# vr60.net
KiCad netlist of a schematic drawn in EAGLE
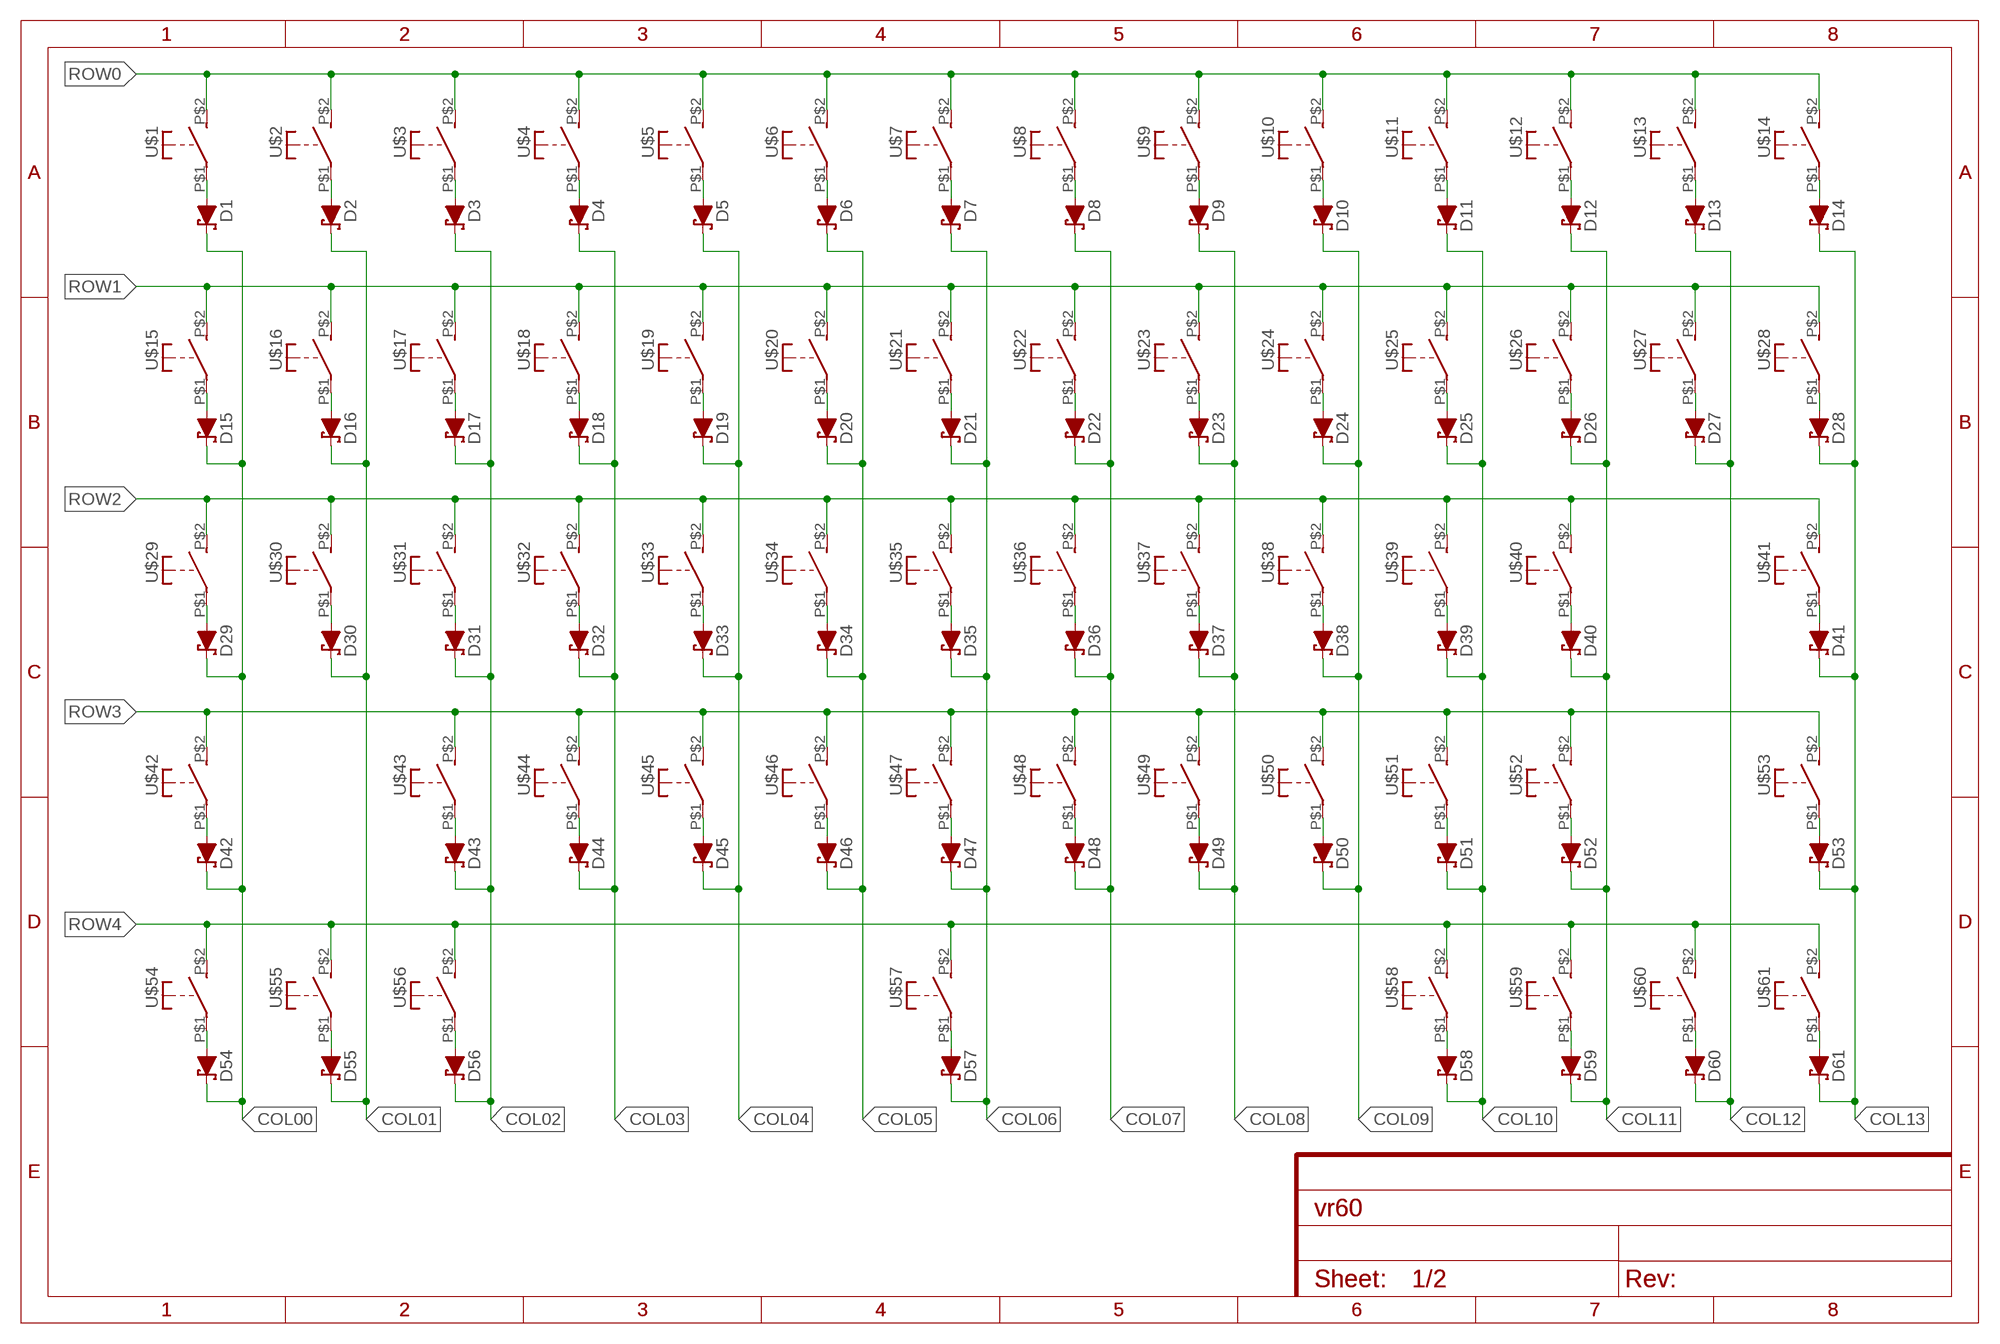
[diagram p0: schematic, sheet 1]
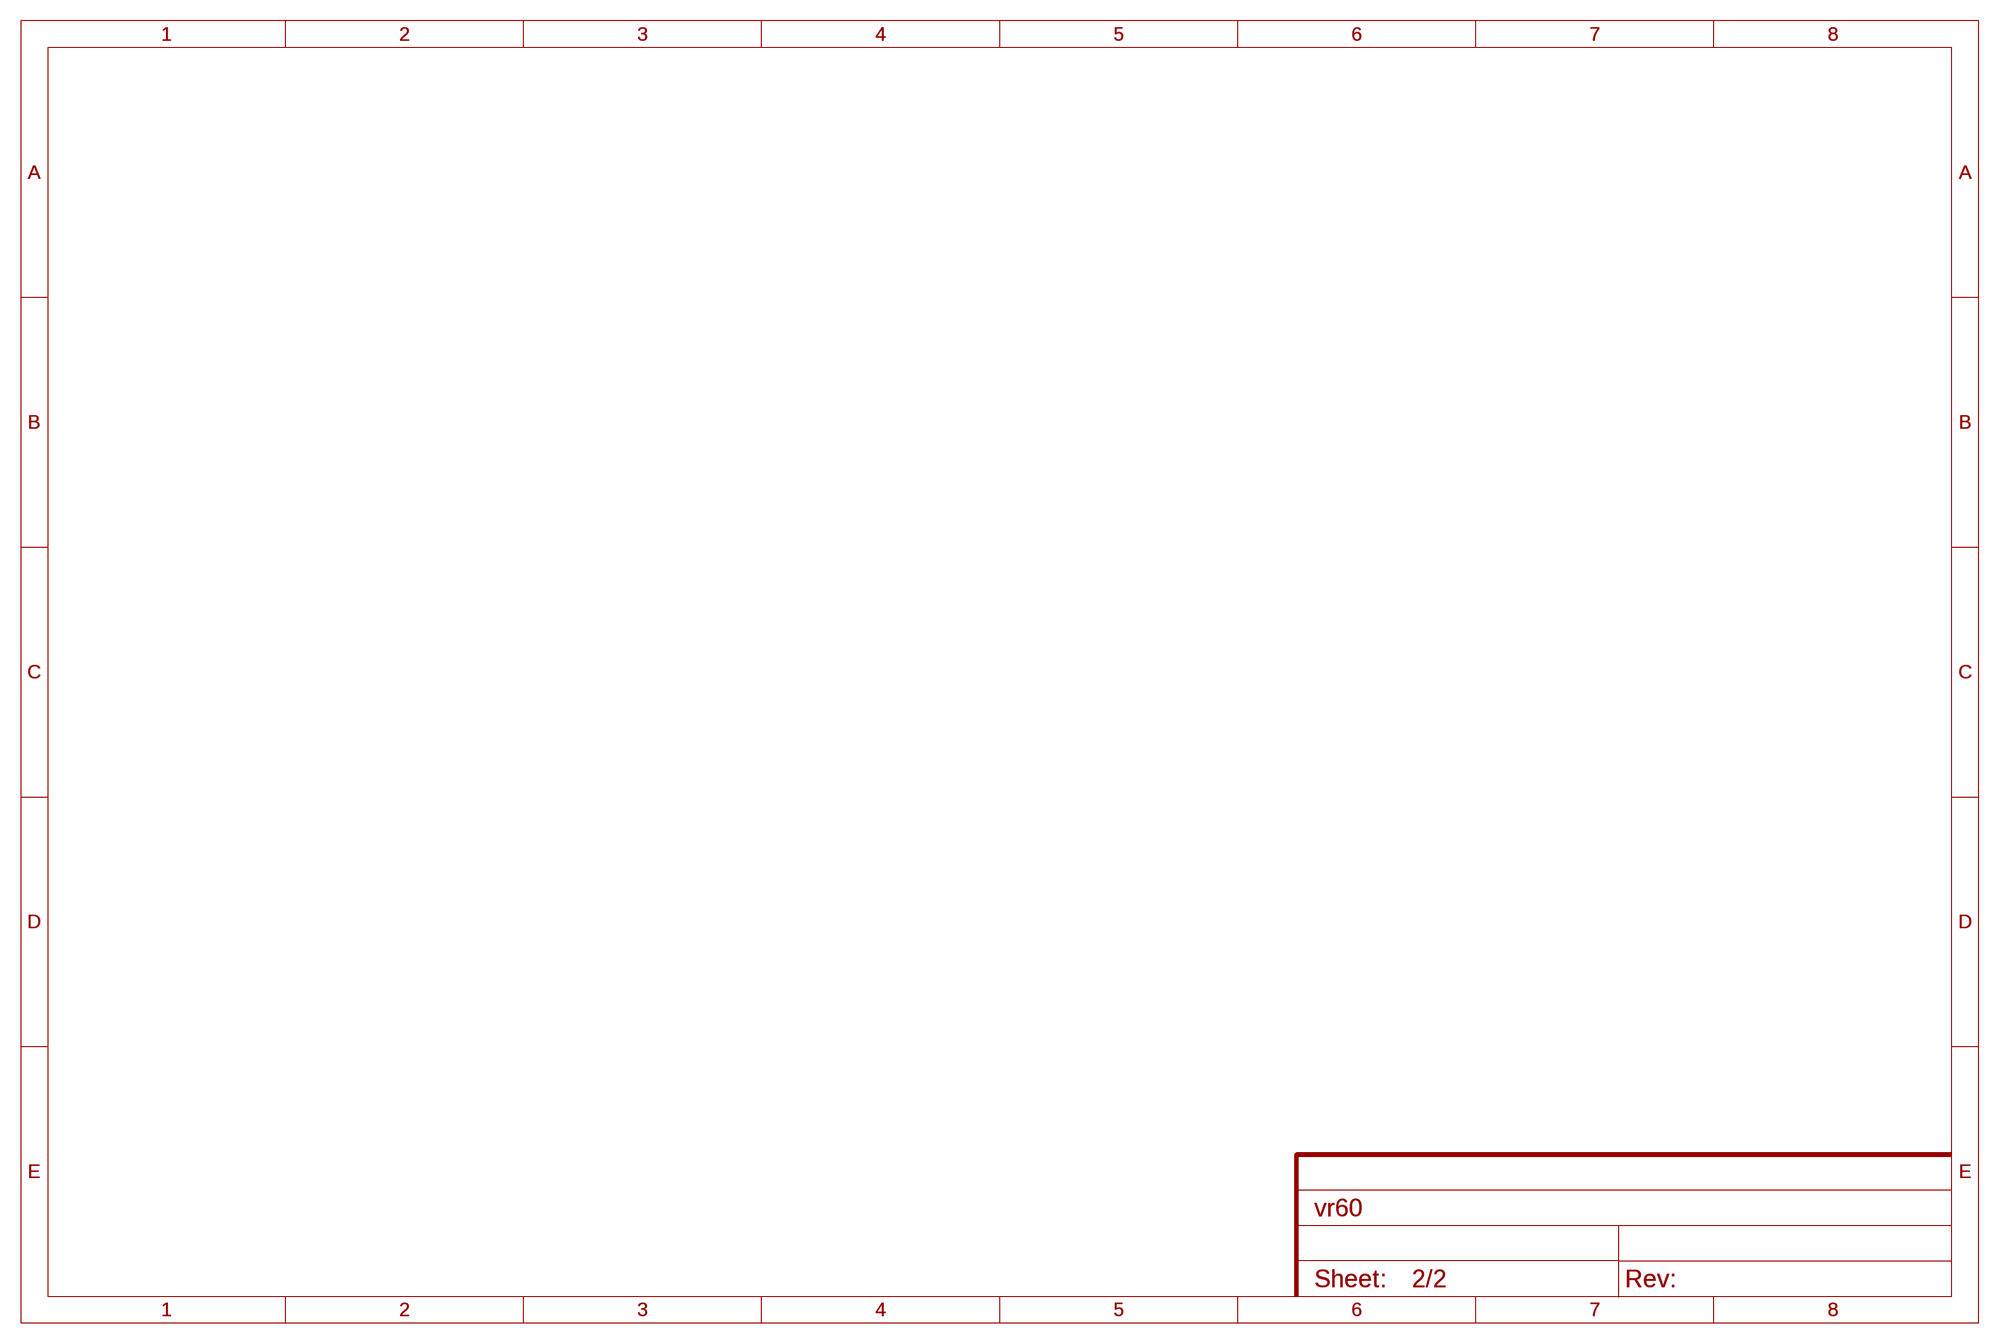
[diagram p1: schematic, sheet 2]

(export (version "E")
  (design (tool "Eeschema 10.0.6"))
  (components
    (comp (ref "D1")
      (value "1N5819WS")
      (footprint "eagle-import:SOD-123")
      (libsource (lib "eagle-import") (part "1N5819WS"))
    )
    (comp (ref "D2")
      (value "1N5819WS")
      (footprint "eagle-import:SOD-123")
      (libsource (lib "eagle-import") (part "1N5819WS"))
    )
    (comp (ref "D3")
      (value "1N5819WS")
      (footprint "eagle-import:SOD-123")
      (libsource (lib "eagle-import") (part "1N5819WS"))
    )
    (comp (ref "D4")
      (value "1N5819WS")
      (footprint "eagle-import:SOD-123")
      (libsource (lib "eagle-import") (part "1N5819WS"))
    )
    (comp (ref "D5")
      (value "1N5819WS")
      (footprint "eagle-import:SOD-123")
      (libsource (lib "eagle-import") (part "1N5819WS"))
    )
    (comp (ref "D6")
      (value "1N5819WS")
      (footprint "eagle-import:SOD-123")
      (libsource (lib "eagle-import") (part "1N5819WS"))
    )
    (comp (ref "D7")
      (value "1N5819WS")
      (footprint "eagle-import:SOD-123")
      (libsource (lib "eagle-import") (part "1N5819WS"))
    )
    (comp (ref "D8")
      (value "1N5819WS")
      (footprint "eagle-import:SOD-123")
      (libsource (lib "eagle-import") (part "1N5819WS"))
    )
    (comp (ref "D9")
      (value "1N5819WS")
      (footprint "eagle-import:SOD-123")
      (libsource (lib "eagle-import") (part "1N5819WS"))
    )
    (comp (ref "D10")
      (value "1N5819WS")
      (footprint "eagle-import:SOD-123")
      (libsource (lib "eagle-import") (part "1N5819WS"))
    )
    (comp (ref "D11")
      (value "1N5819WS")
      (footprint "eagle-import:SOD-123")
      (libsource (lib "eagle-import") (part "1N5819WS"))
    )
    (comp (ref "D12")
      (value "1N5819WS")
      (footprint "eagle-import:SOD-123")
      (libsource (lib "eagle-import") (part "1N5819WS"))
    )
    (comp (ref "D13")
      (value "1N5819WS")
      (footprint "eagle-import:SOD-123")
      (libsource (lib "eagle-import") (part "1N5819WS"))
    )
    (comp (ref "D14")
      (value "1N5819WS")
      (footprint "eagle-import:SOD-123")
      (libsource (lib "eagle-import") (part "1N5819WS"))
    )
    (comp (ref "D15")
      (value "1N5819WS")
      (footprint "eagle-import:SOD-123")
      (libsource (lib "eagle-import") (part "1N5819WS"))
    )
    (comp (ref "D16")
      (value "1N5819WS")
      (footprint "eagle-import:SOD-123")
      (libsource (lib "eagle-import") (part "1N5819WS"))
    )
    (comp (ref "D17")
      (value "1N5819WS")
      (footprint "eagle-import:SOD-123")
      (libsource (lib "eagle-import") (part "1N5819WS"))
    )
    (comp (ref "D18")
      (value "1N5819WS")
      (footprint "eagle-import:SOD-123")
      (libsource (lib "eagle-import") (part "1N5819WS"))
    )
    (comp (ref "D19")
      (value "1N5819WS")
      (footprint "eagle-import:SOD-123")
      (libsource (lib "eagle-import") (part "1N5819WS"))
    )
    (comp (ref "D20")
      (value "1N5819WS")
      (footprint "eagle-import:SOD-123")
      (libsource (lib "eagle-import") (part "1N5819WS"))
    )
    (comp (ref "D21")
      (value "1N5819WS")
      (footprint "eagle-import:SOD-123")
      (libsource (lib "eagle-import") (part "1N5819WS"))
    )
    (comp (ref "D22")
      (value "1N5819WS")
      (footprint "eagle-import:SOD-123")
      (libsource (lib "eagle-import") (part "1N5819WS"))
    )
    (comp (ref "D23")
      (value "1N5819WS")
      (footprint "eagle-import:SOD-123")
      (libsource (lib "eagle-import") (part "1N5819WS"))
    )
    (comp (ref "D24")
      (value "1N5819WS")
      (footprint "eagle-import:SOD-123")
      (libsource (lib "eagle-import") (part "1N5819WS"))
    )
    (comp (ref "D25")
      (value "1N5819WS")
      (footprint "eagle-import:SOD-123")
      (libsource (lib "eagle-import") (part "1N5819WS"))
    )
    (comp (ref "D26")
      (value "1N5819WS")
      (footprint "eagle-import:SOD-123")
      (libsource (lib "eagle-import") (part "1N5819WS"))
    )
    (comp (ref "D27")
      (value "1N5819WS")
      (footprint "eagle-import:SOD-123")
      (libsource (lib "eagle-import") (part "1N5819WS"))
    )
    (comp (ref "D28")
      (value "1N5819WS")
      (footprint "eagle-import:SOD-123")
      (libsource (lib "eagle-import") (part "1N5819WS"))
    )
    (comp (ref "D29")
      (value "1N5819WS")
      (footprint "eagle-import:SOD-123")
      (libsource (lib "eagle-import") (part "1N5819WS"))
    )
    (comp (ref "D30")
      (value "1N5819WS")
      (footprint "eagle-import:SOD-123")
      (libsource (lib "eagle-import") (part "1N5819WS"))
    )
    (comp (ref "D31")
      (value "1N5819WS")
      (footprint "eagle-import:SOD-123")
      (libsource (lib "eagle-import") (part "1N5819WS"))
    )
    (comp (ref "D32")
      (value "1N5819WS")
      (footprint "eagle-import:SOD-123")
      (libsource (lib "eagle-import") (part "1N5819WS"))
    )
    (comp (ref "D33")
      (value "1N5819WS")
      (footprint "eagle-import:SOD-123")
      (libsource (lib "eagle-import") (part "1N5819WS"))
    )
    (comp (ref "D34")
      (value "1N5819WS")
      (footprint "eagle-import:SOD-123")
      (libsource (lib "eagle-import") (part "1N5819WS"))
    )
    (comp (ref "D35")
      (value "1N5819WS")
      (footprint "eagle-import:SOD-123")
      (libsource (lib "eagle-import") (part "1N5819WS"))
    )
    (comp (ref "D36")
      (value "1N5819WS")
      (footprint "eagle-import:SOD-123")
      (libsource (lib "eagle-import") (part "1N5819WS"))
    )
    (comp (ref "D37")
      (value "1N5819WS")
      (footprint "eagle-import:SOD-123")
      (libsource (lib "eagle-import") (part "1N5819WS"))
    )
    (comp (ref "D38")
      (value "1N5819WS")
      (footprint "eagle-import:SOD-123")
      (libsource (lib "eagle-import") (part "1N5819WS"))
    )
    (comp (ref "D39")
      (value "1N5819WS")
      (footprint "eagle-import:SOD-123")
      (libsource (lib "eagle-import") (part "1N5819WS"))
    )
    (comp (ref "D40")
      (value "1N5819WS")
      (footprint "eagle-import:SOD-123")
      (libsource (lib "eagle-import") (part "1N5819WS"))
    )
    (comp (ref "D41")
      (value "1N5819WS")
      (footprint "eagle-import:SOD-123")
      (libsource (lib "eagle-import") (part "1N5819WS"))
    )
    (comp (ref "D42")
      (value "1N5819WS")
      (footprint "eagle-import:SOD-123")
      (libsource (lib "eagle-import") (part "1N5819WS"))
    )
    (comp (ref "D43")
      (value "1N5819WS")
      (footprint "eagle-import:SOD-123")
      (libsource (lib "eagle-import") (part "1N5819WS"))
    )
    (comp (ref "D44")
      (value "1N5819WS")
      (footprint "eagle-import:SOD-123")
      (libsource (lib "eagle-import") (part "1N5819WS"))
    )
    (comp (ref "D45")
      (value "1N5819WS")
      (footprint "eagle-import:SOD-123")
      (libsource (lib "eagle-import") (part "1N5819WS"))
    )
    (comp (ref "D46")
      (value "1N5819WS")
      (footprint "eagle-import:SOD-123")
      (libsource (lib "eagle-import") (part "1N5819WS"))
    )
    (comp (ref "D47")
      (value "1N5819WS")
      (footprint "eagle-import:SOD-123")
      (libsource (lib "eagle-import") (part "1N5819WS"))
    )
    (comp (ref "D48")
      (value "1N5819WS")
      (footprint "eagle-import:SOD-123")
      (libsource (lib "eagle-import") (part "1N5819WS"))
    )
    (comp (ref "D49")
      (value "1N5819WS")
      (footprint "eagle-import:SOD-123")
      (libsource (lib "eagle-import") (part "1N5819WS"))
    )
    (comp (ref "D50")
      (value "1N5819WS")
      (footprint "eagle-import:SOD-123")
      (libsource (lib "eagle-import") (part "1N5819WS"))
    )
    (comp (ref "D51")
      (value "1N5819WS")
      (footprint "eagle-import:SOD-123")
      (libsource (lib "eagle-import") (part "1N5819WS"))
    )
    (comp (ref "D52")
      (value "1N5819WS")
      (footprint "eagle-import:SOD-123")
      (libsource (lib "eagle-import") (part "1N5819WS"))
    )
    (comp (ref "D53")
      (value "1N5819WS")
      (footprint "eagle-import:SOD-123")
      (libsource (lib "eagle-import") (part "1N5819WS"))
    )
    (comp (ref "D54")
      (value "1N5819WS")
      (footprint "eagle-import:SOD-123")
      (libsource (lib "eagle-import") (part "1N5819WS"))
    )
    (comp (ref "D55")
      (value "1N5819WS")
      (footprint "eagle-import:SOD-123")
      (libsource (lib "eagle-import") (part "1N5819WS"))
    )
    (comp (ref "D56")
      (value "1N5819WS")
      (footprint "eagle-import:SOD-123")
      (libsource (lib "eagle-import") (part "1N5819WS"))
    )
    (comp (ref "D57")
      (value "1N5819WS")
      (footprint "eagle-import:SOD-123")
      (libsource (lib "eagle-import") (part "1N5819WS"))
    )
    (comp (ref "D58")
      (value "1N5819WS")
      (footprint "eagle-import:SOD-123")
      (libsource (lib "eagle-import") (part "1N5819WS"))
    )
    (comp (ref "D59")
      (value "1N5819WS")
      (footprint "eagle-import:SOD-123")
      (libsource (lib "eagle-import") (part "1N5819WS"))
    )
    (comp (ref "D60")
      (value "1N5819WS")
      (footprint "eagle-import:SOD-123")
      (libsource (lib "eagle-import") (part "1N5819WS"))
    )
    (comp (ref "D61")
      (value "1N5819WS")
      (footprint "eagle-import:SOD-123")
      (libsource (lib "eagle-import") (part "1N5819WS"))
    )
    (comp (ref "U$1")
      (value "MX-5-PIN-HOTSWAP")
      (footprint "eagle-import:MX-5-PIN-HOTSWAP")
      (libsource (lib "eagle-import") (part "MX-5-PIN-HOTSWAP"))
    )
    (comp (ref "U$2")
      (value "MX-5-PIN-HOTSWAP")
      (footprint "eagle-import:MX-5-PIN-HOTSWAP")
      (libsource (lib "eagle-import") (part "MX-5-PIN-HOTSWAP"))
    )
    (comp (ref "U$3")
      (value "MX-5-PIN-HOTSWAP")
      (footprint "eagle-import:MX-5-PIN-HOTSWAP")
      (libsource (lib "eagle-import") (part "MX-5-PIN-HOTSWAP"))
    )
    (comp (ref "U$4")
      (value "MX-5-PIN-HOTSWAP")
      (footprint "eagle-import:MX-5-PIN-HOTSWAP")
      (libsource (lib "eagle-import") (part "MX-5-PIN-HOTSWAP"))
    )
    (comp (ref "U$5")
      (value "MX-5-PIN-HOTSWAP")
      (footprint "eagle-import:MX-5-PIN-HOTSWAP")
      (libsource (lib "eagle-import") (part "MX-5-PIN-HOTSWAP"))
    )
    (comp (ref "U$6")
      (value "MX-5-PIN-HOTSWAP")
      (footprint "eagle-import:MX-5-PIN-HOTSWAP")
      (libsource (lib "eagle-import") (part "MX-5-PIN-HOTSWAP"))
    )
    (comp (ref "U$7")
      (value "MX-5-PIN-HOTSWAP")
      (footprint "eagle-import:MX-5-PIN-HOTSWAP")
      (libsource (lib "eagle-import") (part "MX-5-PIN-HOTSWAP"))
    )
    (comp (ref "U$8")
      (value "MX-5-PIN-HOTSWAP")
      (footprint "eagle-import:MX-5-PIN-HOTSWAP")
      (libsource (lib "eagle-import") (part "MX-5-PIN-HOTSWAP"))
    )
    (comp (ref "U$9")
      (value "MX-5-PIN-HOTSWAP")
      (footprint "eagle-import:MX-5-PIN-HOTSWAP")
      (libsource (lib "eagle-import") (part "MX-5-PIN-HOTSWAP"))
    )
    (comp (ref "U$10")
      (value "MX-5-PIN-HOTSWAP")
      (footprint "eagle-import:MX-5-PIN-HOTSWAP")
      (libsource (lib "eagle-import") (part "MX-5-PIN-HOTSWAP"))
    )
    (comp (ref "U$11")
      (value "MX-5-PIN-HOTSWAP")
      (footprint "eagle-import:MX-5-PIN-HOTSWAP")
      (libsource (lib "eagle-import") (part "MX-5-PIN-HOTSWAP"))
    )
    (comp (ref "U$12")
      (value "MX-5-PIN-HOTSWAP")
      (footprint "eagle-import:MX-5-PIN-HOTSWAP")
      (libsource (lib "eagle-import") (part "MX-5-PIN-HOTSWAP"))
    )
    (comp (ref "U$13")
      (value "MX-5-PIN-HOTSWAP")
      (footprint "eagle-import:MX-5-PIN-HOTSWAP")
      (libsource (lib "eagle-import") (part "MX-5-PIN-HOTSWAP"))
    )
    (comp (ref "U$14")
      (value "MX-5-PIN-HOTSWAP")
      (footprint "eagle-import:MX-5-PIN-HOTSWAP")
      (libsource (lib "eagle-import") (part "MX-5-PIN-HOTSWAP"))
    )
    (comp (ref "U$15")
      (value "MX-5-PIN-HOTSWAP")
      (footprint "eagle-import:MX-5-PIN-HOTSWAP")
      (libsource (lib "eagle-import") (part "MX-5-PIN-HOTSWAP"))
    )
    (comp (ref "U$16")
      (value "MX-5-PIN-HOTSWAP")
      (footprint "eagle-import:MX-5-PIN-HOTSWAP")
      (libsource (lib "eagle-import") (part "MX-5-PIN-HOTSWAP"))
    )
    (comp (ref "U$17")
      (value "MX-5-PIN-HOTSWAP")
      (footprint "eagle-import:MX-5-PIN-HOTSWAP")
      (libsource (lib "eagle-import") (part "MX-5-PIN-HOTSWAP"))
    )
    (comp (ref "U$18")
      (value "MX-5-PIN-HOTSWAP")
      (footprint "eagle-import:MX-5-PIN-HOTSWAP")
      (libsource (lib "eagle-import") (part "MX-5-PIN-HOTSWAP"))
    )
    (comp (ref "U$19")
      (value "MX-5-PIN-HOTSWAP")
      (footprint "eagle-import:MX-5-PIN-HOTSWAP")
      (libsource (lib "eagle-import") (part "MX-5-PIN-HOTSWAP"))
    )
    (comp (ref "U$20")
      (value "MX-5-PIN-HOTSWAP")
      (footprint "eagle-import:MX-5-PIN-HOTSWAP")
      (libsource (lib "eagle-import") (part "MX-5-PIN-HOTSWAP"))
    )
    (comp (ref "U$21")
      (value "MX-5-PIN-HOTSWAP")
      (footprint "eagle-import:MX-5-PIN-HOTSWAP")
      (libsource (lib "eagle-import") (part "MX-5-PIN-HOTSWAP"))
    )
    (comp (ref "U$22")
      (value "MX-5-PIN-HOTSWAP")
      (footprint "eagle-import:MX-5-PIN-HOTSWAP")
      (libsource (lib "eagle-import") (part "MX-5-PIN-HOTSWAP"))
    )
    (comp (ref "U$23")
      (value "MX-5-PIN-HOTSWAP")
      (footprint "eagle-import:MX-5-PIN-HOTSWAP")
      (libsource (lib "eagle-import") (part "MX-5-PIN-HOTSWAP"))
    )
    (comp (ref "U$24")
      (value "MX-5-PIN-HOTSWAP")
      (footprint "eagle-import:MX-5-PIN-HOTSWAP")
      (libsource (lib "eagle-import") (part "MX-5-PIN-HOTSWAP"))
    )
    (comp (ref "U$25")
      (value "MX-5-PIN-HOTSWAP")
      (footprint "eagle-import:MX-5-PIN-HOTSWAP")
      (libsource (lib "eagle-import") (part "MX-5-PIN-HOTSWAP"))
    )
    (comp (ref "U$26")
      (value "MX-5-PIN-HOTSWAP")
      (footprint "eagle-import:MX-5-PIN-HOTSWAP")
      (libsource (lib "eagle-import") (part "MX-5-PIN-HOTSWAP"))
    )
    (comp (ref "U$27")
      (value "MX-5-PIN-HOTSWAP")
      (footprint "eagle-import:MX-5-PIN-HOTSWAP")
      (libsource (lib "eagle-import") (part "MX-5-PIN-HOTSWAP"))
    )
    (comp (ref "U$28")
      (value "MX-5-PIN-HOTSWAP")
      (footprint "eagle-import:MX-5-PIN-HOTSWAP")
      (libsource (lib "eagle-import") (part "MX-5-PIN-HOTSWAP"))
    )
    (comp (ref "U$29")
      (value "MX-5-PIN-HOTSWAP")
      (footprint "eagle-import:MX-5-PIN-HOTSWAP")
      (libsource (lib "eagle-import") (part "MX-5-PIN-HOTSWAP"))
    )
    (comp (ref "U$30")
      (value "MX-5-PIN-HOTSWAP")
      (footprint "eagle-import:MX-5-PIN-HOTSWAP")
      (libsource (lib "eagle-import") (part "MX-5-PIN-HOTSWAP"))
    )
    (comp (ref "U$31")
      (value "MX-5-PIN-HOTSWAP")
      (footprint "eagle-import:MX-5-PIN-HOTSWAP")
      (libsource (lib "eagle-import") (part "MX-5-PIN-HOTSWAP"))
    )
    (comp (ref "U$32")
      (value "MX-5-PIN-HOTSWAP")
      (footprint "eagle-import:MX-5-PIN-HOTSWAP")
      (libsource (lib "eagle-import") (part "MX-5-PIN-HOTSWAP"))
    )
    (comp (ref "U$33")
      (value "MX-5-PIN-HOTSWAP")
      (footprint "eagle-import:MX-5-PIN-HOTSWAP")
      (libsource (lib "eagle-import") (part "MX-5-PIN-HOTSWAP"))
    )
    (comp (ref "U$34")
      (value "MX-5-PIN-HOTSWAP")
      (footprint "eagle-import:MX-5-PIN-HOTSWAP")
      (libsource (lib "eagle-import") (part "MX-5-PIN-HOTSWAP"))
    )
    (comp (ref "U$35")
      (value "MX-5-PIN-HOTSWAP")
      (footprint "eagle-import:MX-5-PIN-HOTSWAP")
      (libsource (lib "eagle-import") (part "MX-5-PIN-HOTSWAP"))
    )
    (comp (ref "U$36")
      (value "MX-5-PIN-HOTSWAP")
      (footprint "eagle-import:MX-5-PIN-HOTSWAP")
      (libsource (lib "eagle-import") (part "MX-5-PIN-HOTSWAP"))
    )
    (comp (ref "U$37")
      (value "MX-5-PIN-HOTSWAP")
      (footprint "eagle-import:MX-5-PIN-HOTSWAP")
      (libsource (lib "eagle-import") (part "MX-5-PIN-HOTSWAP"))
    )
    (comp (ref "U$38")
      (value "MX-5-PIN-HOTSWAP")
      (footprint "eagle-import:MX-5-PIN-HOTSWAP")
      (libsource (lib "eagle-import") (part "MX-5-PIN-HOTSWAP"))
    )
    (comp (ref "U$39")
      (value "MX-5-PIN-HOTSWAP")
      (footprint "eagle-import:MX-5-PIN-HOTSWAP")
      (libsource (lib "eagle-import") (part "MX-5-PIN-HOTSWAP"))
    )
    (comp (ref "U$40")
      (value "MX-5-PIN-HOTSWAP")
      (footprint "eagle-import:MX-5-PIN-HOTSWAP")
      (libsource (lib "eagle-import") (part "MX-5-PIN-HOTSWAP"))
    )
    (comp (ref "U$41")
      (value "MX-5-PIN-HOTSWAP")
      (footprint "eagle-import:MX-5-PIN-HOTSWAP")
      (libsource (lib "eagle-import") (part "MX-5-PIN-HOTSWAP"))
    )
    (comp (ref "U$42")
      (value "MX-5-PIN-HOTSWAP")
      (footprint "eagle-import:MX-5-PIN-HOTSWAP")
      (libsource (lib "eagle-import") (part "MX-5-PIN-HOTSWAP"))
    )
    (comp (ref "U$43")
      (value "MX-5-PIN-HOTSWAP")
      (footprint "eagle-import:MX-5-PIN-HOTSWAP")
      (libsource (lib "eagle-import") (part "MX-5-PIN-HOTSWAP"))
    )
    (comp (ref "U$44")
      (value "MX-5-PIN-HOTSWAP")
      (footprint "eagle-import:MX-5-PIN-HOTSWAP")
      (libsource (lib "eagle-import") (part "MX-5-PIN-HOTSWAP"))
    )
    (comp (ref "U$45")
      (value "MX-5-PIN-HOTSWAP")
      (footprint "eagle-import:MX-5-PIN-HOTSWAP")
      (libsource (lib "eagle-import") (part "MX-5-PIN-HOTSWAP"))
    )
    (comp (ref "U$46")
      (value "MX-5-PIN-HOTSWAP")
      (footprint "eagle-import:MX-5-PIN-HOTSWAP")
      (libsource (lib "eagle-import") (part "MX-5-PIN-HOTSWAP"))
    )
    (comp (ref "U$47")
      (value "MX-5-PIN-HOTSWAP")
      (footprint "eagle-import:MX-5-PIN-HOTSWAP")
      (libsource (lib "eagle-import") (part "MX-5-PIN-HOTSWAP"))
    )
    (comp (ref "U$48")
      (value "MX-5-PIN-HOTSWAP")
      (footprint "eagle-import:MX-5-PIN-HOTSWAP")
      (libsource (lib "eagle-import") (part "MX-5-PIN-HOTSWAP"))
    )
    (comp (ref "U$49")
      (value "MX-5-PIN-HOTSWAP")
      (footprint "eagle-import:MX-5-PIN-HOTSWAP")
      (libsource (lib "eagle-import") (part "MX-5-PIN-HOTSWAP"))
    )
    (comp (ref "U$50")
      (value "MX-5-PIN-HOTSWAP")
      (footprint "eagle-import:MX-5-PIN-HOTSWAP")
      (libsource (lib "eagle-import") (part "MX-5-PIN-HOTSWAP"))
    )
    (comp (ref "U$51")
      (value "MX-5-PIN-HOTSWAP")
      (footprint "eagle-import:MX-5-PIN-HOTSWAP")
      (libsource (lib "eagle-import") (part "MX-5-PIN-HOTSWAP"))
    )
    (comp (ref "U$52")
      (value "MX-5-PIN-HOTSWAP")
      (footprint "eagle-import:MX-5-PIN-HOTSWAP")
      (libsource (lib "eagle-import") (part "MX-5-PIN-HOTSWAP"))
    )
    (comp (ref "U$53")
      (value "MX-5-PIN-HOTSWAP")
      (footprint "eagle-import:MX-5-PIN-HOTSWAP")
      (libsource (lib "eagle-import") (part "MX-5-PIN-HOTSWAP"))
    )
    (comp (ref "U$54")
      (value "MX-5-PIN-HOTSWAP")
      (footprint "eagle-import:MX-5-PIN-HOTSWAP")
      (libsource (lib "eagle-import") (part "MX-5-PIN-HOTSWAP"))
    )
    (comp (ref "U$55")
      (value "MX-5-PIN-HOTSWAP")
      (footprint "eagle-import:MX-5-PIN-HOTSWAP")
      (libsource (lib "eagle-import") (part "MX-5-PIN-HOTSWAP"))
    )
    (comp (ref "U$56")
      (value "MX-5-PIN-HOTSWAP")
      (footprint "eagle-import:MX-5-PIN-HOTSWAP")
      (libsource (lib "eagle-import") (part "MX-5-PIN-HOTSWAP"))
    )
    (comp (ref "U$57")
      (value "MX-5-PIN-HOTSWAP")
      (footprint "eagle-import:MX-5-PIN-HOTSWAP")
      (libsource (lib "eagle-import") (part "MX-5-PIN-HOTSWAP"))
    )
    (comp (ref "U$58")
      (value "MX-5-PIN-HOTSWAP")
      (footprint "eagle-import:MX-5-PIN-HOTSWAP")
      (libsource (lib "eagle-import") (part "MX-5-PIN-HOTSWAP"))
    )
    (comp (ref "U$59")
      (value "MX-5-PIN-HOTSWAP")
      (footprint "eagle-import:MX-5-PIN-HOTSWAP")
      (libsource (lib "eagle-import") (part "MX-5-PIN-HOTSWAP"))
    )
    (comp (ref "U$60")
      (value "MX-5-PIN-HOTSWAP")
      (footprint "eagle-import:MX-5-PIN-HOTSWAP")
      (libsource (lib "eagle-import") (part "MX-5-PIN-HOTSWAP"))
    )
    (comp (ref "U$61")
      (value "MX-5-PIN-HOTSWAP")
      (footprint "eagle-import:MX-5-PIN-HOTSWAP")
      (libsource (lib "eagle-import") (part "MX-5-PIN-HOTSWAP"))
    )
  )
  (nets
    (net (code "1") (name "COL00") (class "Default")
      (node (ref "D1") (pin "C") (pinfunction "C_C") (pintype "passive"))
      (node (ref "D15") (pin "C") (pinfunction "C_C") (pintype "passive"))
      (node (ref "D29") (pin "C") (pinfunction "C_C") (pintype "passive"))
      (node (ref "D42") (pin "C") (pinfunction "C_C") (pintype "passive"))
      (node (ref "D54") (pin "C") (pinfunction "C_C") (pintype "passive"))
    )
    (net (code "2") (name "COL01") (class "Default")
      (node (ref "D16") (pin "C") (pinfunction "C_C") (pintype "passive"))
      (node (ref "D2") (pin "C") (pinfunction "C_C") (pintype "passive"))
      (node (ref "D30") (pin "C") (pinfunction "C_C") (pintype "passive"))
      (node (ref "D55") (pin "C") (pinfunction "C_C") (pintype "passive"))
    )
    (net (code "3") (name "COL02") (class "Default")
      (node (ref "D17") (pin "C") (pinfunction "C_C") (pintype "passive"))
      (node (ref "D3") (pin "C") (pinfunction "C_C") (pintype "passive"))
      (node (ref "D31") (pin "C") (pinfunction "C_C") (pintype "passive"))
      (node (ref "D43") (pin "C") (pinfunction "C_C") (pintype "passive"))
      (node (ref "D56") (pin "C") (pinfunction "C_C") (pintype "passive"))
    )
    (net (code "4") (name "COL03") (class "Default")
      (node (ref "D18") (pin "C") (pinfunction "C_C") (pintype "passive"))
      (node (ref "D32") (pin "C") (pinfunction "C_C") (pintype "passive"))
      (node (ref "D4") (pin "C") (pinfunction "C_C") (pintype "passive"))
      (node (ref "D44") (pin "C") (pinfunction "C_C") (pintype "passive"))
    )
    (net (code "5") (name "COL04") (class "Default")
      (node (ref "D19") (pin "C") (pinfunction "C_C") (pintype "passive"))
      (node (ref "D33") (pin "C") (pinfunction "C_C") (pintype "passive"))
      (node (ref "D45") (pin "C") (pinfunction "C_C") (pintype "passive"))
      (node (ref "D5") (pin "C") (pinfunction "C_C") (pintype "passive"))
    )
    (net (code "6") (name "COL05") (class "Default")
      (node (ref "D20") (pin "C") (pinfunction "C_C") (pintype "passive"))
      (node (ref "D34") (pin "C") (pinfunction "C_C") (pintype "passive"))
      (node (ref "D46") (pin "C") (pinfunction "C_C") (pintype "passive"))
      (node (ref "D6") (pin "C") (pinfunction "C_C") (pintype "passive"))
    )
    (net (code "7") (name "COL06") (class "Default")
      (node (ref "D21") (pin "C") (pinfunction "C_C") (pintype "passive"))
      (node (ref "D35") (pin "C") (pinfunction "C_C") (pintype "passive"))
      (node (ref "D47") (pin "C") (pinfunction "C_C") (pintype "passive"))
      (node (ref "D57") (pin "C") (pinfunction "C_C") (pintype "passive"))
      (node (ref "D7") (pin "C") (pinfunction "C_C") (pintype "passive"))
    )
    (net (code "8") (name "COL07") (class "Default")
      (node (ref "D22") (pin "C") (pinfunction "C_C") (pintype "passive"))
      (node (ref "D36") (pin "C") (pinfunction "C_C") (pintype "passive"))
      (node (ref "D48") (pin "C") (pinfunction "C_C") (pintype "passive"))
      (node (ref "D8") (pin "C") (pinfunction "C_C") (pintype "passive"))
    )
    (net (code "9") (name "COL08") (class "Default")
      (node (ref "D23") (pin "C") (pinfunction "C_C") (pintype "passive"))
      (node (ref "D37") (pin "C") (pinfunction "C_C") (pintype "passive"))
      (node (ref "D49") (pin "C") (pinfunction "C_C") (pintype "passive"))
      (node (ref "D9") (pin "C") (pinfunction "C_C") (pintype "passive"))
    )
    (net (code "10") (name "COL09") (class "Default")
      (node (ref "D10") (pin "C") (pinfunction "C_C") (pintype "passive"))
      (node (ref "D24") (pin "C") (pinfunction "C_C") (pintype "passive"))
      (node (ref "D38") (pin "C") (pinfunction "C_C") (pintype "passive"))
      (node (ref "D50") (pin "C") (pinfunction "C_C") (pintype "passive"))
    )
    (net (code "11") (name "COL10") (class "Default")
      (node (ref "D11") (pin "C") (pinfunction "C_C") (pintype "passive"))
      (node (ref "D25") (pin "C") (pinfunction "C_C") (pintype "passive"))
      (node (ref "D39") (pin "C") (pinfunction "C_C") (pintype "passive"))
      (node (ref "D51") (pin "C") (pinfunction "C_C") (pintype "passive"))
      (node (ref "D58") (pin "C") (pinfunction "C_C") (pintype "passive"))
    )
    (net (code "12") (name "COL11") (class "Default")
      (node (ref "D12") (pin "C") (pinfunction "C_C") (pintype "passive"))
      (node (ref "D26") (pin "C") (pinfunction "C_C") (pintype "passive"))
      (node (ref "D40") (pin "C") (pinfunction "C_C") (pintype "passive"))
      (node (ref "D52") (pin "C") (pinfunction "C_C") (pintype "passive"))
      (node (ref "D59") (pin "C") (pinfunction "C_C") (pintype "passive"))
    )
    (net (code "13") (name "COL12") (class "Default")
      (node (ref "D13") (pin "C") (pinfunction "C_C") (pintype "passive"))
      (node (ref "D27") (pin "C") (pinfunction "C_C") (pintype "passive"))
      (node (ref "D60") (pin "C") (pinfunction "C_C") (pintype "passive"))
    )
    (net (code "14") (name "COL13") (class "Default")
      (node (ref "D14") (pin "C") (pinfunction "C_C") (pintype "passive"))
      (node (ref "D28") (pin "C") (pinfunction "C_C") (pintype "passive"))
      (node (ref "D41") (pin "C") (pinfunction "C_C") (pintype "passive"))
      (node (ref "D53") (pin "C") (pinfunction "C_C") (pintype "passive"))
      (node (ref "D61") (pin "C") (pinfunction "C_C") (pintype "passive"))
    )
    (net (code "15") (name "Net-(U$1-P)") (class "Default")
      (node (ref "D1") (pin "A") (pinfunction "A_A") (pintype "passive"))
      (node (ref "U$1") (pin "P$1") (pinfunction "P_P$1") (pintype "passive"))
    )
    (net (code "16") (name "Net-(U$2-P)") (class "Default")
      (node (ref "D2") (pin "A") (pinfunction "A_A") (pintype "passive"))
      (node (ref "U$2") (pin "P$1") (pinfunction "P_P$1") (pintype "passive"))
    )
    (net (code "17") (name "Net-(U$3-P)") (class "Default")
      (node (ref "D3") (pin "A") (pinfunction "A_A") (pintype "passive"))
      (node (ref "U$3") (pin "P$1") (pinfunction "P_P$1") (pintype "passive"))
    )
    (net (code "18") (name "Net-(U$4-P)") (class "Default")
      (node (ref "D4") (pin "A") (pinfunction "A_A") (pintype "passive"))
      (node (ref "U$4") (pin "P$1") (pinfunction "P_P$1") (pintype "passive"))
    )
    (net (code "19") (name "Net-(U$5-P)") (class "Default")
      (node (ref "D5") (pin "A") (pinfunction "A_A") (pintype "passive"))
      (node (ref "U$5") (pin "P$1") (pinfunction "P_P$1") (pintype "passive"))
    )
    (net (code "20") (name "Net-(U$6-P)") (class "Default")
      (node (ref "D6") (pin "A") (pinfunction "A_A") (pintype "passive"))
      (node (ref "U$6") (pin "P$1") (pinfunction "P_P$1") (pintype "passive"))
    )
    (net (code "21") (name "Net-(U$7-P)") (class "Default")
      (node (ref "D7") (pin "A") (pinfunction "A_A") (pintype "passive"))
      (node (ref "U$7") (pin "P$1") (pinfunction "P_P$1") (pintype "passive"))
    )
    (net (code "22") (name "Net-(U$8-P)") (class "Default")
      (node (ref "D8") (pin "A") (pinfunction "A_A") (pintype "passive"))
      (node (ref "U$8") (pin "P$1") (pinfunction "P_P$1") (pintype "passive"))
    )
    (net (code "23") (name "Net-(U$9-P)") (class "Default")
      (node (ref "D9") (pin "A") (pinfunction "A_A") (pintype "passive"))
      (node (ref "U$9") (pin "P$1") (pinfunction "P_P$1") (pintype "passive"))
    )
    (net (code "24") (name "Net-(U$10-P)") (class "Default")
      (node (ref "D10") (pin "A") (pinfunction "A_A") (pintype "passive"))
      (node (ref "U$10") (pin "P$1") (pinfunction "P_P$1") (pintype "passive"))
    )
    (net (code "25") (name "Net-(U$11-P)") (class "Default")
      (node (ref "D11") (pin "A") (pinfunction "A_A") (pintype "passive"))
      (node (ref "U$11") (pin "P$1") (pinfunction "P_P$1") (pintype "passive"))
    )
    (net (code "26") (name "Net-(U$12-P)") (class "Default")
      (node (ref "D12") (pin "A") (pinfunction "A_A") (pintype "passive"))
      (node (ref "U$12") (pin "P$1") (pinfunction "P_P$1") (pintype "passive"))
    )
    (net (code "27") (name "Net-(U$13-P)") (class "Default")
      (node (ref "D13") (pin "A") (pinfunction "A_A") (pintype "passive"))
      (node (ref "U$13") (pin "P$1") (pinfunction "P_P$1") (pintype "passive"))
    )
    (net (code "28") (name "Net-(U$14-P)") (class "Default")
      (node (ref "D14") (pin "A") (pinfunction "A_A") (pintype "passive"))
      (node (ref "U$14") (pin "P$1") (pinfunction "P_P$1") (pintype "passive"))
    )
    (net (code "29") (name "Net-(U$15-P)") (class "Default")
      (node (ref "D15") (pin "A") (pinfunction "A_A") (pintype "passive"))
      (node (ref "U$15") (pin "P$1") (pinfunction "P_P$1") (pintype "passive"))
    )
    (net (code "30") (name "Net-(U$16-P)") (class "Default")
      (node (ref "D16") (pin "A") (pinfunction "A_A") (pintype "passive"))
      (node (ref "U$16") (pin "P$1") (pinfunction "P_P$1") (pintype "passive"))
    )
    (net (code "31") (name "Net-(U$17-P)") (class "Default")
      (node (ref "D17") (pin "A") (pinfunction "A_A") (pintype "passive"))
      (node (ref "U$17") (pin "P$1") (pinfunction "P_P$1") (pintype "passive"))
    )
    (net (code "32") (name "Net-(U$18-P)") (class "Default")
      (node (ref "D18") (pin "A") (pinfunction "A_A") (pintype "passive"))
      (node (ref "U$18") (pin "P$1") (pinfunction "P_P$1") (pintype "passive"))
    )
    (net (code "33") (name "Net-(U$19-P)") (class "Default")
      (node (ref "D19") (pin "A") (pinfunction "A_A") (pintype "passive"))
      (node (ref "U$19") (pin "P$1") (pinfunction "P_P$1") (pintype "passive"))
    )
    (net (code "34") (name "Net-(U$20-P)") (class "Default")
      (node (ref "D20") (pin "A") (pinfunction "A_A") (pintype "passive"))
      (node (ref "U$20") (pin "P$1") (pinfunction "P_P$1") (pintype "passive"))
    )
    (net (code "35") (name "Net-(U$21-P)") (class "Default")
      (node (ref "D21") (pin "A") (pinfunction "A_A") (pintype "passive"))
      (node (ref "U$21") (pin "P$1") (pinfunction "P_P$1") (pintype "passive"))
    )
    (net (code "36") (name "Net-(U$22-P)") (class "Default")
      (node (ref "D22") (pin "A") (pinfunction "A_A") (pintype "passive"))
      (node (ref "U$22") (pin "P$1") (pinfunction "P_P$1") (pintype "passive"))
    )
    (net (code "37") (name "Net-(U$23-P)") (class "Default")
      (node (ref "D23") (pin "A") (pinfunction "A_A") (pintype "passive"))
      (node (ref "U$23") (pin "P$1") (pinfunction "P_P$1") (pintype "passive"))
    )
    (net (code "38") (name "Net-(U$24-P)") (class "Default")
      (node (ref "D24") (pin "A") (pinfunction "A_A") (pintype "passive"))
      (node (ref "U$24") (pin "P$1") (pinfunction "P_P$1") (pintype "passive"))
    )
    (net (code "39") (name "Net-(U$25-P)") (class "Default")
      (node (ref "D25") (pin "A") (pinfunction "A_A") (pintype "passive"))
      (node (ref "U$25") (pin "P$1") (pinfunction "P_P$1") (pintype "passive"))
    )
    (net (code "40") (name "Net-(U$26-P)") (class "Default")
      (node (ref "D26") (pin "A") (pinfunction "A_A") (pintype "passive"))
      (node (ref "U$26") (pin "P$1") (pinfunction "P_P$1") (pintype "passive"))
    )
    (net (code "41") (name "Net-(U$27-P)") (class "Default")
      (node (ref "D27") (pin "A") (pinfunction "A_A") (pintype "passive"))
      (node (ref "U$27") (pin "P$1") (pinfunction "P_P$1") (pintype "passive"))
    )
    (net (code "42") (name "Net-(U$28-P)") (class "Default")
      (node (ref "D28") (pin "A") (pinfunction "A_A") (pintype "passive"))
      (node (ref "U$28") (pin "P$1") (pinfunction "P_P$1") (pintype "passive"))
    )
    (net (code "43") (name "Net-(U$29-P)") (class "Default")
      (node (ref "D29") (pin "A") (pinfunction "A_A") (pintype "passive"))
      (node (ref "U$29") (pin "P$1") (pinfunction "P_P$1") (pintype "passive"))
    )
    (net (code "44") (name "Net-(U$30-P)") (class "Default")
      (node (ref "D30") (pin "A") (pinfunction "A_A") (pintype "passive"))
      (node (ref "U$30") (pin "P$1") (pinfunction "P_P$1") (pintype "passive"))
    )
    (net (code "45") (name "Net-(U$31-P)") (class "Default")
      (node (ref "D31") (pin "A") (pinfunction "A_A") (pintype "passive"))
      (node (ref "U$31") (pin "P$1") (pinfunction "P_P$1") (pintype "passive"))
    )
    (net (code "46") (name "Net-(U$32-P)") (class "Default")
      (node (ref "D32") (pin "A") (pinfunction "A_A") (pintype "passive"))
      (node (ref "U$32") (pin "P$1") (pinfunction "P_P$1") (pintype "passive"))
    )
    (net (code "47") (name "Net-(U$33-P)") (class "Default")
      (node (ref "D33") (pin "A") (pinfunction "A_A") (pintype "passive"))
      (node (ref "U$33") (pin "P$1") (pinfunction "P_P$1") (pintype "passive"))
    )
    (net (code "48") (name "Net-(U$34-P)") (class "Default")
      (node (ref "D34") (pin "A") (pinfunction "A_A") (pintype "passive"))
      (node (ref "U$34") (pin "P$1") (pinfunction "P_P$1") (pintype "passive"))
    )
    (net (code "49") (name "Net-(U$35-P)") (class "Default")
      (node (ref "D35") (pin "A") (pinfunction "A_A") (pintype "passive"))
      (node (ref "U$35") (pin "P$1") (pinfunction "P_P$1") (pintype "passive"))
    )
    (net (code "50") (name "Net-(U$36-P)") (class "Default")
      (node (ref "D36") (pin "A") (pinfunction "A_A") (pintype "passive"))
      (node (ref "U$36") (pin "P$1") (pinfunction "P_P$1") (pintype "passive"))
    )
    (net (code "51") (name "Net-(U$37-P)") (class "Default")
      (node (ref "D37") (pin "A") (pinfunction "A_A") (pintype "passive"))
      (node (ref "U$37") (pin "P$1") (pinfunction "P_P$1") (pintype "passive"))
    )
    (net (code "52") (name "Net-(U$38-P)") (class "Default")
      (node (ref "D38") (pin "A") (pinfunction "A_A") (pintype "passive"))
      (node (ref "U$38") (pin "P$1") (pinfunction "P_P$1") (pintype "passive"))
    )
    (net (code "53") (name "Net-(U$39-P)") (class "Default")
      (node (ref "D39") (pin "A") (pinfunction "A_A") (pintype "passive"))
      (node (ref "U$39") (pin "P$1") (pinfunction "P_P$1") (pintype "passive"))
    )
    (net (code "54") (name "Net-(U$40-P)") (class "Default")
      (node (ref "D40") (pin "A") (pinfunction "A_A") (pintype "passive"))
      (node (ref "U$40") (pin "P$1") (pinfunction "P_P$1") (pintype "passive"))
    )
    (net (code "55") (name "Net-(U$41-P)") (class "Default")
      (node (ref "D41") (pin "A") (pinfunction "A_A") (pintype "passive"))
      (node (ref "U$41") (pin "P$1") (pinfunction "P_P$1") (pintype "passive"))
    )
    (net (code "56") (name "Net-(U$42-P)") (class "Default")
      (node (ref "D42") (pin "A") (pinfunction "A_A") (pintype "passive"))
      (node (ref "U$42") (pin "P$1") (pinfunction "P_P$1") (pintype "passive"))
    )
    (net (code "57") (name "Net-(U$43-P)") (class "Default")
      (node (ref "D43") (pin "A") (pinfunction "A_A") (pintype "passive"))
      (node (ref "U$43") (pin "P$1") (pinfunction "P_P$1") (pintype "passive"))
    )
    (net (code "58") (name "Net-(U$44-P)") (class "Default")
      (node (ref "D44") (pin "A") (pinfunction "A_A") (pintype "passive"))
      (node (ref "U$44") (pin "P$1") (pinfunction "P_P$1") (pintype "passive"))
    )
    (net (code "59") (name "Net-(U$45-P)") (class "Default")
      (node (ref "D45") (pin "A") (pinfunction "A_A") (pintype "passive"))
      (node (ref "U$45") (pin "P$1") (pinfunction "P_P$1") (pintype "passive"))
    )
    (net (code "60") (name "Net-(U$46-P)") (class "Default")
      (node (ref "D46") (pin "A") (pinfunction "A_A") (pintype "passive"))
      (node (ref "U$46") (pin "P$1") (pinfunction "P_P$1") (pintype "passive"))
    )
    (net (code "61") (name "Net-(U$47-P)") (class "Default")
      (node (ref "D47") (pin "A") (pinfunction "A_A") (pintype "passive"))
      (node (ref "U$47") (pin "P$1") (pinfunction "P_P$1") (pintype "passive"))
    )
    (net (code "62") (name "Net-(U$48-P)") (class "Default")
      (node (ref "D48") (pin "A") (pinfunction "A_A") (pintype "passive"))
      (node (ref "U$48") (pin "P$1") (pinfunction "P_P$1") (pintype "passive"))
    )
    (net (code "63") (name "Net-(U$49-P)") (class "Default")
      (node (ref "D49") (pin "A") (pinfunction "A_A") (pintype "passive"))
      (node (ref "U$49") (pin "P$1") (pinfunction "P_P$1") (pintype "passive"))
    )
    (net (code "64") (name "Net-(U$50-P)") (class "Default")
      (node (ref "D50") (pin "A") (pinfunction "A_A") (pintype "passive"))
      (node (ref "U$50") (pin "P$1") (pinfunction "P_P$1") (pintype "passive"))
    )
    (net (code "65") (name "Net-(U$51-P)") (class "Default")
      (node (ref "D51") (pin "A") (pinfunction "A_A") (pintype "passive"))
      (node (ref "U$51") (pin "P$1") (pinfunction "P_P$1") (pintype "passive"))
    )
    (net (code "66") (name "Net-(U$52-P)") (class "Default")
      (node (ref "D52") (pin "A") (pinfunction "A_A") (pintype "passive"))
      (node (ref "U$52") (pin "P$1") (pinfunction "P_P$1") (pintype "passive"))
    )
    (net (code "67") (name "Net-(U$53-P)") (class "Default")
      (node (ref "D53") (pin "A") (pinfunction "A_A") (pintype "passive"))
      (node (ref "U$53") (pin "P$1") (pinfunction "P_P$1") (pintype "passive"))
    )
    (net (code "68") (name "Net-(U$54-P)") (class "Default")
      (node (ref "D54") (pin "A") (pinfunction "A_A") (pintype "passive"))
      (node (ref "U$54") (pin "P$1") (pinfunction "P_P$1") (pintype "passive"))
    )
    (net (code "69") (name "Net-(U$55-P)") (class "Default")
      (node (ref "D55") (pin "A") (pinfunction "A_A") (pintype "passive"))
      (node (ref "U$55") (pin "P$1") (pinfunction "P_P$1") (pintype "passive"))
    )
    (net (code "70") (name "Net-(U$56-P)") (class "Default")
      (node (ref "D56") (pin "A") (pinfunction "A_A") (pintype "passive"))
      (node (ref "U$56") (pin "P$1") (pinfunction "P_P$1") (pintype "passive"))
    )
    (net (code "71") (name "Net-(U$57-P)") (class "Default")
      (node (ref "D57") (pin "A") (pinfunction "A_A") (pintype "passive"))
      (node (ref "U$57") (pin "P$1") (pinfunction "P_P$1") (pintype "passive"))
    )
    (net (code "72") (name "Net-(U$58-P)") (class "Default")
      (node (ref "D58") (pin "A") (pinfunction "A_A") (pintype "passive"))
      (node (ref "U$58") (pin "P$1") (pinfunction "P_P$1") (pintype "passive"))
    )
    (net (code "73") (name "Net-(U$59-P)") (class "Default")
      (node (ref "D59") (pin "A") (pinfunction "A_A") (pintype "passive"))
      (node (ref "U$59") (pin "P$1") (pinfunction "P_P$1") (pintype "passive"))
    )
    (net (code "74") (name "Net-(U$60-P)") (class "Default")
      (node (ref "D60") (pin "A") (pinfunction "A_A") (pintype "passive"))
      (node (ref "U$60") (pin "P$1") (pinfunction "P_P$1") (pintype "passive"))
    )
    (net (code "75") (name "Net-(U$61-P)") (class "Default")
      (node (ref "D61") (pin "A") (pinfunction "A_A") (pintype "passive"))
      (node (ref "U$61") (pin "P$1") (pinfunction "P_P$1") (pintype "passive"))
    )
    (net (code "76") (name "ROW0") (class "Default")
      (node (ref "U$1") (pin "P$2") (pinfunction "S_P$2") (pintype "passive"))
      (node (ref "U$10") (pin "P$2") (pinfunction "S_P$2") (pintype "passive"))
      (node (ref "U$11") (pin "P$2") (pinfunction "S_P$2") (pintype "passive"))
      (node (ref "U$12") (pin "P$2") (pinfunction "S_P$2") (pintype "passive"))
      (node (ref "U$13") (pin "P$2") (pinfunction "S_P$2") (pintype "passive"))
      (node (ref "U$14") (pin "P$2") (pinfunction "S_P$2") (pintype "passive"))
      (node (ref "U$2") (pin "P$2") (pinfunction "S_P$2") (pintype "passive"))
      (node (ref "U$3") (pin "P$2") (pinfunction "S_P$2") (pintype "passive"))
      (node (ref "U$4") (pin "P$2") (pinfunction "S_P$2") (pintype "passive"))
      (node (ref "U$5") (pin "P$2") (pinfunction "S_P$2") (pintype "passive"))
      (node (ref "U$6") (pin "P$2") (pinfunction "S_P$2") (pintype "passive"))
      (node (ref "U$7") (pin "P$2") (pinfunction "S_P$2") (pintype "passive"))
      (node (ref "U$8") (pin "P$2") (pinfunction "S_P$2") (pintype "passive"))
      (node (ref "U$9") (pin "P$2") (pinfunction "S_P$2") (pintype "passive"))
    )
    (net (code "77") (name "ROW1") (class "Default")
      (node (ref "U$15") (pin "P$2") (pinfunction "S_P$2") (pintype "passive"))
      (node (ref "U$16") (pin "P$2") (pinfunction "S_P$2") (pintype "passive"))
      (node (ref "U$17") (pin "P$2") (pinfunction "S_P$2") (pintype "passive"))
      (node (ref "U$18") (pin "P$2") (pinfunction "S_P$2") (pintype "passive"))
      (node (ref "U$19") (pin "P$2") (pinfunction "S_P$2") (pintype "passive"))
      (node (ref "U$20") (pin "P$2") (pinfunction "S_P$2") (pintype "passive"))
      (node (ref "U$21") (pin "P$2") (pinfunction "S_P$2") (pintype "passive"))
      (node (ref "U$22") (pin "P$2") (pinfunction "S_P$2") (pintype "passive"))
      (node (ref "U$23") (pin "P$2") (pinfunction "S_P$2") (pintype "passive"))
      (node (ref "U$24") (pin "P$2") (pinfunction "S_P$2") (pintype "passive"))
      (node (ref "U$25") (pin "P$2") (pinfunction "S_P$2") (pintype "passive"))
      (node (ref "U$26") (pin "P$2") (pinfunction "S_P$2") (pintype "passive"))
      (node (ref "U$27") (pin "P$2") (pinfunction "S_P$2") (pintype "passive"))
      (node (ref "U$28") (pin "P$2") (pinfunction "S_P$2") (pintype "passive"))
    )
    (net (code "78") (name "ROW2") (class "Default")
      (node (ref "U$29") (pin "P$2") (pinfunction "S_P$2") (pintype "passive"))
      (node (ref "U$30") (pin "P$2") (pinfunction "S_P$2") (pintype "passive"))
      (node (ref "U$31") (pin "P$2") (pinfunction "S_P$2") (pintype "passive"))
      (node (ref "U$32") (pin "P$2") (pinfunction "S_P$2") (pintype "passive"))
      (node (ref "U$33") (pin "P$2") (pinfunction "S_P$2") (pintype "passive"))
      (node (ref "U$34") (pin "P$2") (pinfunction "S_P$2") (pintype "passive"))
      (node (ref "U$35") (pin "P$2") (pinfunction "S_P$2") (pintype "passive"))
      (node (ref "U$36") (pin "P$2") (pinfunction "S_P$2") (pintype "passive"))
      (node (ref "U$37") (pin "P$2") (pinfunction "S_P$2") (pintype "passive"))
      (node (ref "U$38") (pin "P$2") (pinfunction "S_P$2") (pintype "passive"))
      (node (ref "U$39") (pin "P$2") (pinfunction "S_P$2") (pintype "passive"))
      (node (ref "U$40") (pin "P$2") (pinfunction "S_P$2") (pintype "passive"))
      (node (ref "U$41") (pin "P$2") (pinfunction "S_P$2") (pintype "passive"))
    )
    (net (code "79") (name "ROW3") (class "Default")
      (node (ref "U$42") (pin "P$2") (pinfunction "S_P$2") (pintype "passive"))
      (node (ref "U$43") (pin "P$2") (pinfunction "S_P$2") (pintype "passive"))
      (node (ref "U$44") (pin "P$2") (pinfunction "S_P$2") (pintype "passive"))
      (node (ref "U$45") (pin "P$2") (pinfunction "S_P$2") (pintype "passive"))
      (node (ref "U$46") (pin "P$2") (pinfunction "S_P$2") (pintype "passive"))
      (node (ref "U$47") (pin "P$2") (pinfunction "S_P$2") (pintype "passive"))
      (node (ref "U$48") (pin "P$2") (pinfunction "S_P$2") (pintype "passive"))
      (node (ref "U$49") (pin "P$2") (pinfunction "S_P$2") (pintype "passive"))
      (node (ref "U$50") (pin "P$2") (pinfunction "S_P$2") (pintype "passive"))
      (node (ref "U$51") (pin "P$2") (pinfunction "S_P$2") (pintype "passive"))
      (node (ref "U$52") (pin "P$2") (pinfunction "S_P$2") (pintype "passive"))
      (node (ref "U$53") (pin "P$2") (pinfunction "S_P$2") (pintype "passive"))
    )
    (net (code "80") (name "ROW4") (class "Default")
      (node (ref "U$54") (pin "P$2") (pinfunction "S_P$2") (pintype "passive"))
      (node (ref "U$55") (pin "P$2") (pinfunction "S_P$2") (pintype "passive"))
      (node (ref "U$56") (pin "P$2") (pinfunction "S_P$2") (pintype "passive"))
      (node (ref "U$57") (pin "P$2") (pinfunction "S_P$2") (pintype "passive"))
      (node (ref "U$58") (pin "P$2") (pinfunction "S_P$2") (pintype "passive"))
      (node (ref "U$59") (pin "P$2") (pinfunction "S_P$2") (pintype "passive"))
      (node (ref "U$60") (pin "P$2") (pinfunction "S_P$2") (pintype "passive"))
      (node (ref "U$61") (pin "P$2") (pinfunction "S_P$2") (pintype "passive"))
    )
  )
)
